# Auto_Switch.net
KiCad netlist of a schematic drawn in Altium Designer
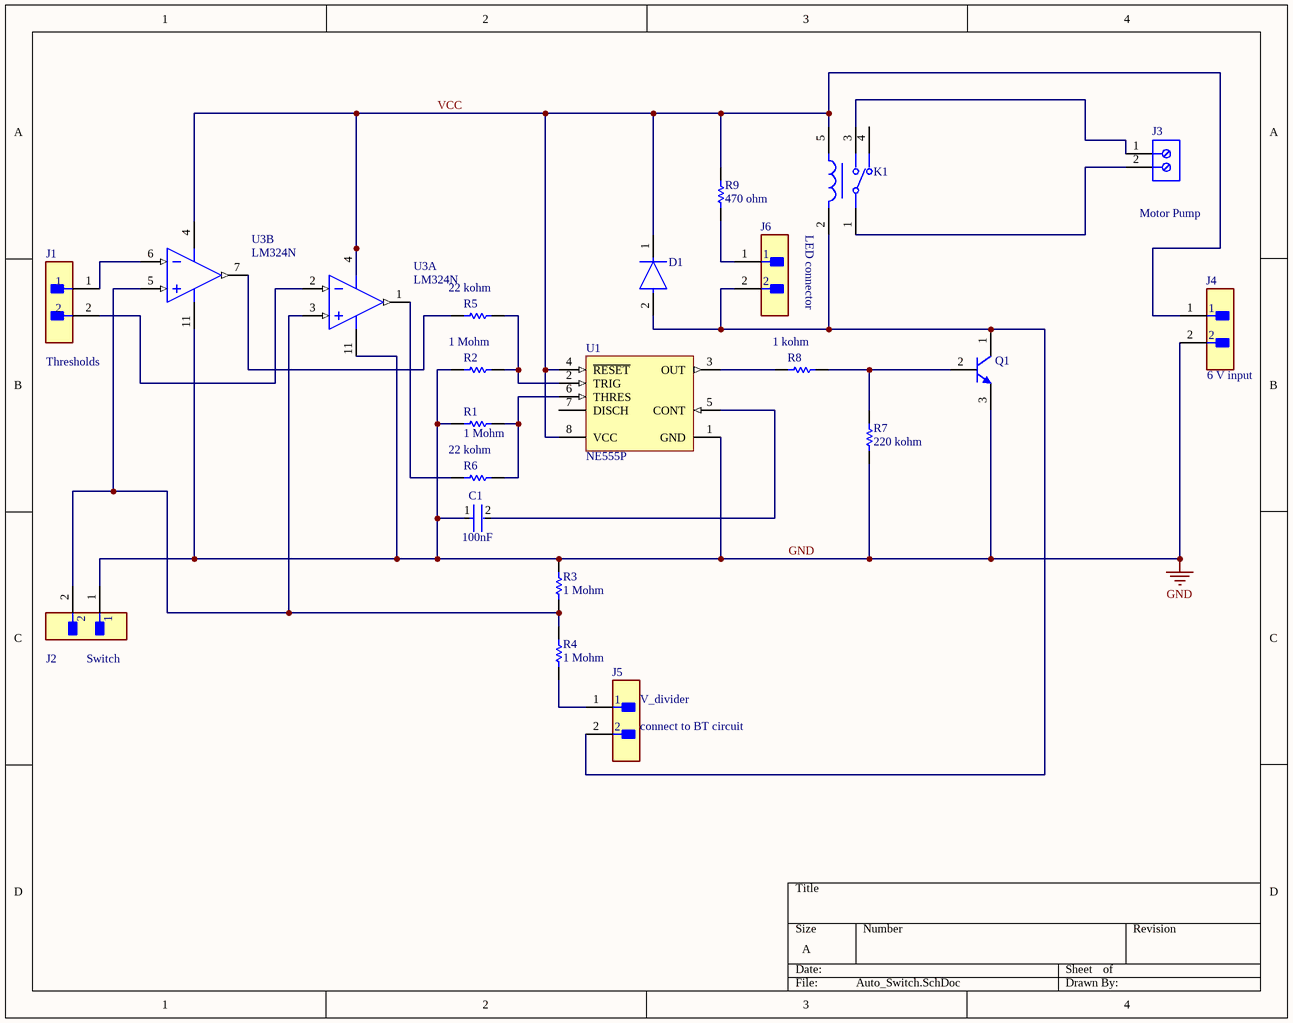
[diagram p0: Auto_Switch.SchDoc]

(export (version "E")
  (design (tool "Eeschema 10.0.6"))
  (components
    (comp (ref "C1")
      (value "RDER72E104K2K1H03B")
      (footprint "FP-RDE2M1-MFG")
      (description "Ceramic Capacitor 100nF ±10% 250V X7R Radial")
      (fields (field (name "TOLERANCE") "10%") (field (name "CAPACITANCE") "100nF"))
      (libsource (lib "Altium Content Vault") (part "b4654b650e69147ec39a6b967a45e02"))
    )
    (comp (ref "D1")
      (value "1N4007-E3/54")
      (footprint "FP-1N4007-MFG")
      (description "DIODE GEN PURP 1KV 1A DO204AL")
      (fields
        (field (name "OCTOPART") "https://octopart.com/1n4007-e3%2F54-vishay-39548207")
        (field (name "MANUFACTURER") "Vishay")
      )
      (libsource (lib "Altium Content Vault") (part "d7152d700b627762746794eb795d46e"))
    )
    (comp (ref "J1")
      (value "TSW-102-07-L-S")
      (footprint "FP-TSW-102-07-L-S-MFG")
      (description "CONN HEADER VERT 2POS 2.54MM")
      (libsource (lib "") (part "3bc925449376181038e59eaffc5286c_1"))
    )
    (comp (ref "J2")
      (value "TSW-102-07-L-S")
      (footprint "FP-TSW-102-07-L-S-MFG")
      (description "CONN HEADER VERT 2POS 2.54MM")
      (libsource (lib "") (part "3bc925449376181038e59eaffc5286c_1"))
    )
    (comp (ref "J3")
      (value "691101710002")
      (footprint "691101710002")
      (description "Series 101 - 5.00 mm Horizontal Entry Modular with Pressure Clamp WR-TBL, 2 pin")
      (fields (field (name "MANUFACTURER") "Wurth Elektronik") (field (name "PUBLISHER") "WurthElektronik"))
      (libsource (lib "Altium Content Vault") (part "WE-CN-1P-F-TB2"))
    )
    (comp (ref "J4")
      (value "TSW-102-07-L-S")
      (footprint "FP-TSW-102-07-L-S-MFG")
      (description "CONN HEADER VERT 2POS 2.54MM")
      (libsource (lib "Altium Content Vault") (part "3bc925449376181038e59eaffc5286c"))
    )
    (comp (ref "J5")
      (value "TSW-102-07-L-S")
      (footprint "FP-TSW-102-07-L-S-MFG")
      (description "CONN HEADER VERT 2POS 2.54MM")
      (libsource (lib "Altium Content Vault") (part "3bc925449376181038e59eaffc5286c"))
    )
    (comp (ref "J6")
      (value "TSW-102-07-L-S")
      (footprint "FP-TSW-102-07-L-S-MFG")
      (description "CONN HEADER VERT 2POS 2.54MM")
      (libsource (lib "Altium Content Vault") (part "3bc925449376181038e59eaffc5286c"))
    )
    (comp (ref "K1")
      (value "G5LE-14-DC5")
      (footprint "FP-G5LE-14-DC5-MFG")
      (description "RELAY GEN PURPOSE SPDT 10A 5V")
      (fields
        (field (name "OCTOPART") "https://octopart.com/g5le-14-dc5-omron-28829")
        (field (name "MANUFACTURER") "Omron")
      )
      (libsource (lib "Altium Content Vault") (part "c03b8d08e5d02e70a6880f365e34168"))
    )
    (comp (ref "Q1")
      (value "BC547B")
      (footprint "ONSC-TO-92-3-29-11")
      (description "Amplifier Transistor, NPN Silicon, 3-Pin TO-92, Bulk Box")
      (fields (field (name "MANUFACTURER") "On Semiconductor"))
      (libsource (lib "Altium Content Vault") (part "ONSC-NPN-C1B2E3-3"))
    )
    (comp (ref "R1")
      (value "MFR-25FBF52-1M")
      (footprint "RESA60-630X240")
      (description "Axial Resistor, 1 MOhm, +/- 1%, 250 mW, -55 to 155 degC, 2-Pin THD, RoHS, Bulk")
      (fields (field (name "RESISTANCE") "1 Mohm") (field (name "TOLERANCE") "1%"))
      (libsource (lib "Altium Content Vault") (part "RES-2"))
    )
    (comp (ref "R2")
      (value "MFR-25FBF52-1M")
      (footprint "RESA60-630X240")
      (description "Axial Resistor, 1 MOhm, +/- 1%, 250 mW, -55 to 155 degC, 2-Pin THD, RoHS, Bulk")
      (fields (field (name "RESISTANCE") "1 Mohm") (field (name "TOLERANCE") "1%"))
      (libsource (lib "Altium Content Vault") (part "RES-2"))
    )
    (comp (ref "R3")
      (value "MFR-25FBF52-1M")
      (footprint "RESA60-630X240")
      (description "Axial Resistor, 1 MOhm, +/- 1%, 250 mW, -55 to 155 degC, 2-Pin THD, RoHS, Bulk")
      (fields (field (name "RESISTANCE") "1 Mohm") (field (name "TOLERANCE") "1%"))
      (libsource (lib "Altium Content Vault") (part "RES-2"))
    )
    (comp (ref "R4")
      (value "MFR-25FBF52-1M")
      (footprint "RESA60-630X240")
      (description "Axial Resistor, 1 MOhm, +/- 1%, 250 mW, -55 to 155 degC, 2-Pin THD, RoHS, Bulk")
      (fields (field (name "RESISTANCE") "1 Mohm") (field (name "TOLERANCE") "1%"))
      (libsource (lib "Altium Content Vault") (part "RES-2"))
    )
    (comp (ref "R5")
      (value "MFR-25FBF52-1M")
      (footprint "RESA60-630X240")
      (description "Axial Resistor, 1 MOhm, +/- 1%, 250 mW, -55 to 155 degC, 2-Pin THD, RoHS, Bulk")
      (fields (field (name "RESISTANCE") "22 kohm") (field (name "TOLERANCE") "1%"))
      (libsource (lib "Altium Content Vault") (part "RES-2"))
    )
    (comp (ref "R6")
      (value "MFR-25FBF52-1M")
      (footprint "RESA60-630X240")
      (description "Axial Resistor, 1 MOhm, +/- 1%, 250 mW, -55 to 155 degC, 2-Pin THD, RoHS, Bulk")
      (fields (field (name "RESISTANCE") "22 kohm") (field (name "TOLERANCE") "1%"))
      (libsource (lib "Altium Content Vault") (part "RES-2"))
    )
    (comp (ref "R7")
      (value "MFR-25FBF52-1M")
      (footprint "RESA60-630X240")
      (description "Axial Resistor, 1 MOhm, +/- 1%, 250 mW, -55 to 155 degC, 2-Pin THD, RoHS, Bulk")
      (fields (field (name "RESISTANCE") "220 kohm") (field (name "TOLERANCE") "1%"))
      (libsource (lib "Altium Content Vault") (part "RES-2"))
    )
    (comp (ref "R8")
      (value "MFR-25FBF52-1M")
      (footprint "RESA60-630X240")
      (description "Axial Resistor, 1 MOhm, +/- 1%, 250 mW, -55 to 155 degC, 2-Pin THD, RoHS, Bulk")
      (fields (field (name "RESISTANCE") "1 kohm") (field (name "TOLERANCE") "1%"))
      (libsource (lib "Altium Content Vault") (part "RES-2"))
    )
    (comp (ref "R9")
      (value "MFR-25FBF52-1M")
      (footprint "RESA60-630X240")
      (description "Axial Resistor, 1 MOhm, +/- 1%, 250 mW, -55 to 155 degC, 2-Pin THD, RoHS, Bulk")
      (fields (field (name "RESISTANCE") "470 ohm") (field (name "TOLERANCE") "1%"))
      (libsource (lib "Altium Content Vault") (part "RES-2"))
    )
    (comp (ref "U1")
      (value "NE555P")
      (footprint "P0008A")
      (description "Precision Timer, 4.5 to 16 V, 0 to 70 degC, 8-Pin DIP, Pb-Free, Tube")
      (fields (field (name "MANUFACTURER") "TexasInstruments"))
      (libsource (lib "Altium Content Vault") (part "TI-NE555-P8"))
    )
    (comp (ref "U3")
      (value "LM324N")
      (footprint "N0014A")
      (description "Low Power Quad Operational Amplifier, 14-pin MDIP")
      (fields (field (name "MANUFACTURER") "Texas Instruments"))
      (libsource (lib "Altium Content Vault") (part "AMP-OPA-LM124-14"))
    )
  )
  (nets
    (net (code "1") (name "/VCC") (class "Default")
      (node (ref "D1") (pin "1") (pinfunction "C_1") (pintype "passive"))
      (node (ref "J4") (pin "1") (pinfunction "1_1") (pintype "passive"))
      (node (ref "K1") (pin "5") (pinfunction "5_5") (pintype "passive"))
      (node (ref "R9") (pin "2") (pinfunction "2_2") (pintype "passive"))
      (node (ref "U1") (pin "4") (pinfunction "~{RESET}_4") (pintype "input"))
      (node (ref "U1") (pin "8") (pinfunction "VCC_8") (pintype "power_in"))
      (node (ref "U3") (pin "4") (pinfunction "V+_4") (pintype "power_in"))
    )
    (net (code "2") (name "GND") (class "Default")
      (node (ref "C1") (pin "1") (pinfunction "1_1") (pintype "passive"))
      (node (ref "J2") (pin "1") (pinfunction "1_1") (pintype "passive"))
      (node (ref "J4") (pin "2") (pinfunction "2_2") (pintype "passive"))
      (node (ref "Q1") (pin "3") (pinfunction "E_3") (pintype "passive"))
      (node (ref "R1") (pin "2") (pinfunction "2_2") (pintype "passive"))
      (node (ref "R2") (pin "1") (pinfunction "1_1") (pintype "passive"))
      (node (ref "R3") (pin "2") (pinfunction "2_2") (pintype "passive"))
      (node (ref "R7") (pin "1") (pinfunction "1_1") (pintype "passive"))
      (node (ref "U1") (pin "1") (pinfunction "GND_1") (pintype "power_in"))
      (node (ref "U3") (pin "11") (pinfunction "GND_11") (pintype "power_in"))
    )
    (net (code "3") (name "Net-(D1-A)") (class "Default")
      (node (ref "D1") (pin "2") (pinfunction "A_2") (pintype "passive"))
      (node (ref "J5") (pin "2") (pinfunction "2_2") (pintype "passive"))
      (node (ref "J6") (pin "2") (pinfunction "2_2") (pintype "passive"))
      (node (ref "K1") (pin "2") (pinfunction "2_2") (pintype "passive"))
      (node (ref "Q1") (pin "1") (pinfunction "C_1") (pintype "passive"))
    )
    (net (code "4") (name "Net-(J3-Pad1)") (class "Default")
      (node (ref "J3") (pin "1") (pinfunction "1_1") (pintype "passive"))
      (node (ref "K1") (pin "3") (pinfunction "3_3") (pintype "passive"))
    )
    (net (code "5") (name "Net-(J3-Pad2)") (class "Default")
      (node (ref "J3") (pin "2") (pinfunction "2_2") (pintype "passive"))
      (node (ref "K1") (pin "1") (pinfunction "1_1") (pintype "passive"))
    )
    (net (code "6") (name "Net-(J5-Pad1)") (class "Default")
      (node (ref "J5") (pin "1") (pinfunction "1_1") (pintype "passive"))
      (node (ref "R4") (pin "1") (pinfunction "1_1") (pintype "passive"))
    )
    (net (code "7") (name "Net-(J6-Pad1)") (class "Default")
      (node (ref "J6") (pin "1") (pinfunction "1_1") (pintype "passive"))
      (node (ref "R9") (pin "1") (pinfunction "1_1") (pintype "passive"))
    )
    (net (code "8") (name "Net-(Q1-B)") (class "Default")
      (node (ref "Q1") (pin "2") (pinfunction "B_2") (pintype "passive"))
      (node (ref "R7") (pin "2") (pinfunction "2_2") (pintype "passive"))
      (node (ref "R8") (pin "2") (pinfunction "2_2") (pintype "passive"))
    )
    (net (code "9") (name "Net-(U1-CONT)") (class "Default")
      (node (ref "C1") (pin "2") (pinfunction "2_2") (pintype "passive"))
      (node (ref "U1") (pin "5") (pinfunction "CONT_5") (pintype "input"))
    )
    (net (code "10") (name "Net-(U1-OUT)") (class "Default")
      (node (ref "R8") (pin "1") (pinfunction "1_1") (pintype "passive"))
      (node (ref "U1") (pin "3") (pinfunction "OUT_3") (pintype "output"))
    )
    (net (code "11") (name "Net-(U1-THRES)") (class "Default")
      (node (ref "R1") (pin "1") (pinfunction "1_1") (pintype "passive"))
      (node (ref "R6") (pin "2") (pinfunction "2_2") (pintype "passive"))
      (node (ref "U1") (pin "6") (pinfunction "THRES_6") (pintype "input"))
    )
    (net (code "12") (name "Net-(U1-TRIG)") (class "Default")
      (node (ref "R2") (pin "2") (pinfunction "2_2") (pintype "passive"))
      (node (ref "R5") (pin "2") (pinfunction "2_2") (pintype "passive"))
      (node (ref "U1") (pin "2") (pinfunction "TRIG_2") (pintype "input"))
    )
    (net (code "13") (name "Net-(U3A-IN1+)") (class "Default")
      (node (ref "J2") (pin "2") (pinfunction "2_2") (pintype "passive"))
      (node (ref "R3") (pin "1") (pinfunction "1_1") (pintype "passive"))
      (node (ref "R4") (pin "2") (pinfunction "2_2") (pintype "passive"))
      (node (ref "U3") (pin "3") (pinfunction "IN1+_3") (pintype "input"))
      (node (ref "U3") (pin "5") (pinfunction "IN2+_5") (pintype "input"))
    )
    (net (code "14") (name "Net-(U3A-IN1-)") (class "Default")
      (node (ref "J1") (pin "2") (pinfunction "2_2") (pintype "passive"))
      (node (ref "U3") (pin "2") (pinfunction "IN1-_2") (pintype "input"))
    )
    (net (code "15") (name "Net-(U3A-OUT1)") (class "Default")
      (node (ref "R6") (pin "1") (pinfunction "1_1") (pintype "passive"))
      (node (ref "U3") (pin "1") (pinfunction "OUT1_1") (pintype "output"))
    )
    (net (code "16") (name "Net-(U3B-IN2-)") (class "Default")
      (node (ref "J1") (pin "1") (pinfunction "1_1") (pintype "passive"))
      (node (ref "U3") (pin "6") (pinfunction "IN2-_6") (pintype "input"))
    )
    (net (code "17") (name "Net-(U3B-OUT2)") (class "Default")
      (node (ref "R5") (pin "1") (pinfunction "1_1") (pintype "passive"))
      (node (ref "U3") (pin "7") (pinfunction "OUT2_7") (pintype "output"))
    )
    (net (code "18") (name "unconnected-(K1-Pad4)") (class "Default")
      (node (ref "K1") (pin "4") (pinfunction "4_4") (pintype "passive"))
    )
    (net (code "19") (name "unconnected-(U1-DISCH-Pad7)") (class "Default")
      (node (ref "U1") (pin "7") (pinfunction "DISCH_7") (pintype "open_collector"))
    )
  )
)
